# High-Current_Power_Supply.net
KiCad netlist of a schematic drawn in Altium Designer
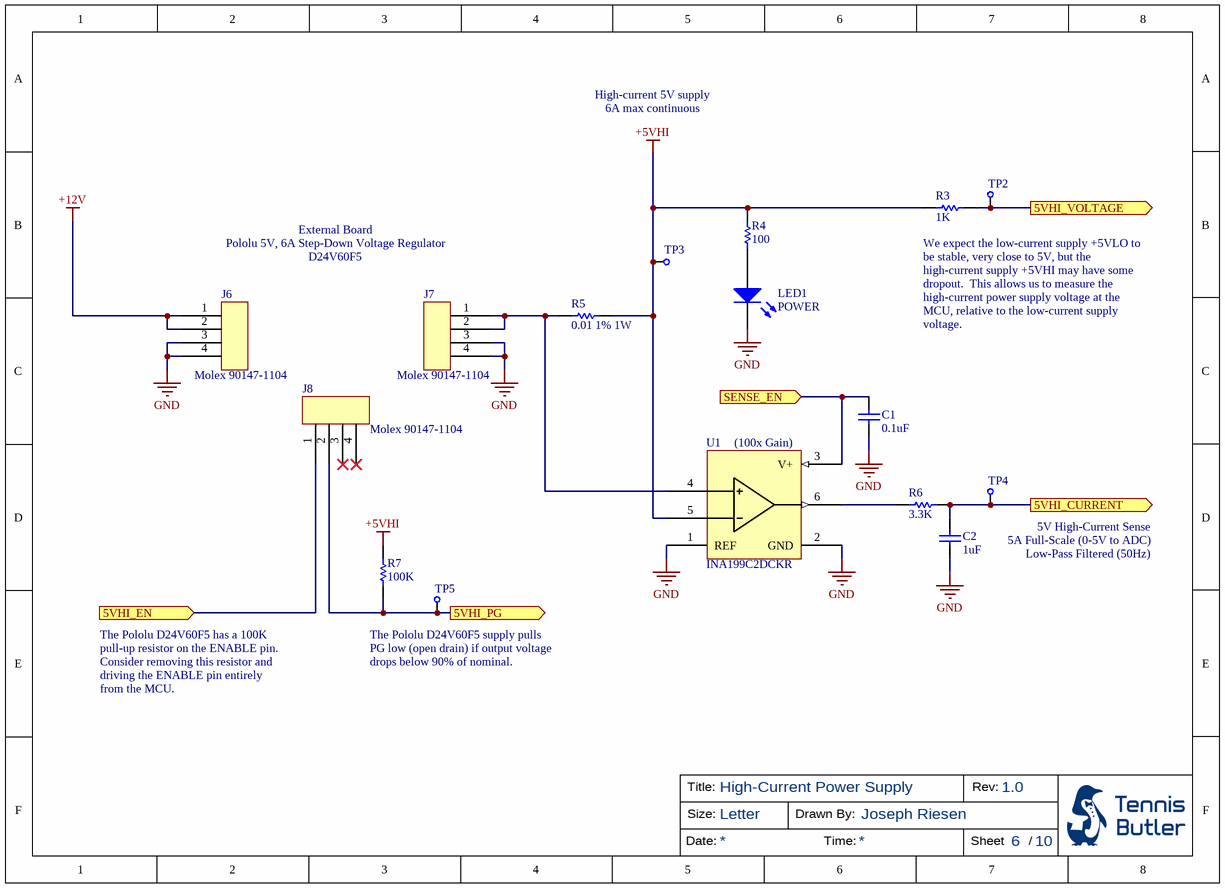
[diagram p0: High-Current Power Supply.SchDoc]

(export (version "E")
  (design (tool "Eeschema 10.0.6"))
  (components
    (comp (ref "C1")
      (value "0.1uF")
      (footprint "CAPC0805(2012)100_M")
      (description "CAP 100nF 6.3V ±10% 0805 (2012 Metric) Thickness 1mm SMD")
      (fields (field (name "TOLERANCE") "Â±10%"))
      (libsource (lib "Altium Content Vault") (part "CAP"))
    )
    (comp (ref "C2")
      (value "1uF")
      (footprint "CAPC2013X100X50ML20T25")
      (fields (field (name "MANUFACTURER") "Kemet") (field (name "PART NUMBER") "C0805C105K9RACTU"))
      (libsource (lib "Altium Content Vault") (part "CAP"))
    )
    (comp (ref "J6")
      (value "Molex 90147-1104")
      (footprint "Molex 90147-1104")
      (description "C-Grid® PC Board Connector, Single Row, Vertical, 4 Circuits, Tin (Sn) Plating")
      (fields (field (name "MANUFACTURER") "Molex") (field (name "MANUFACTURER PART NUMBER") "90147-1104"))
      (libsource (lib "") (part "Molex 90147-1104 C-Grid 4-Pin Header_1"))
    )
    (comp (ref "J7")
      (value "Molex 90147-1104")
      (footprint "Molex 90147-1104")
      (description "C-Grid® PC Board Connector, Single Row, Vertical, 4 Circuits, Tin (Sn) Plating")
      (fields (field (name "MANUFACTURER") "Molex") (field (name "MANUFACTURER PART NUMBER") "90147-1104"))
      (libsource (lib "TennisButler") (part "Molex 90147-1104 C-Grid 4-Pin Header"))
    )
    (comp (ref "J8")
      (value "Molex 90147-1104")
      (footprint "Molex 90147-1104")
      (description "C-Grid® PC Board Connector, Single Row, Vertical, 4 Circuits, Tin (Sn) Plating")
      (fields (field (name "MANUFACTURER") "Molex") (field (name "MANUFACTURER PART NUMBER") "90147-1104"))
      (libsource (lib "") (part "Molex 90147-1104 C-Grid 4-Pin Header_2"))
    )
    (comp (ref "LED1")
      (value "POWER")
      (footprint "0805_A")
      (description "SMD mono-color Chip LED, WL-SMCW, Blue")
      (fields (field (name "MANUFACTURER") "Wuerth Elektronik") (field (name "PARTNUMBER") "150080BS75000"))
      (libsource (lib "Altium Content Vault") (part "WE-LED_K1A2-2"))
    )
    (comp (ref "R3")
      (value "1K")
      (footprint "RESC2013X70X40ML20T20")
      (description "RES SMD 1K OHM 1% 1/8W 0805")
      (fields (field (name "PART NUMBER") "ERJ-6ENF1001V") (field (name "MANUFACTURER") "Panasonic"))
      (libsource (lib "Altium Content Vault") (part "RES"))
    )
    (comp (ref "R4")
      (value "100")
      (footprint "RESC2013X70X40ML20T20")
      (description "Chip Resistor, 100 Ohm, +/- 1%, 0.125 W, -55 to 155 degC, 0805 (2012 Metric), RoHS, Tape and Reel")
      (fields (field (name "MANUFACTURER") "Panasonic"))
      (libsource (lib "Altium Content Vault") (part "RES-2"))
    )
    (comp (ref "R5")
      (value "0.01 1% 1W")
      (footprint "RESC3216X70X50NL05T20")
      (fields (field (name "PART NUMBER") "ERJ8CWFR010V") (field (name "MANUFACTURER") "Panasonic"))
      (libsource (lib "Altium Content Vault") (part "RES"))
    )
    (comp (ref "R6")
      (value "3.3K")
      (footprint "RESC2013X70X40ML20T20")
      (description "RES SMD 3.3K OHM 1% 1/8W 0805")
      (fields (field (name "MANUFACTURER") "Panasonic") (field (name "PART NUMBER") "ERJ6ENF3301V"))
      (libsource (lib "Altium Content Vault") (part "RES"))
    )
    (comp (ref "R7")
      (value "100K")
      (footprint "RESC2013X70X40ML20T20")
      (description "RES SMD 100K OHM 1% 1/8W 0805")
      (fields (field (name "PART NUMBER") "ERJ-6ENF1003V") (field (name "MANUFACTURER") "Panasonic"))
      (libsource (lib "Altium Content Vault") (part "RES"))
    )
    (comp (ref "TP2")
      (value "5VHI VSENSE")
      (footprint "Test Point")
      (libsource (lib "Miscellaneous") (part "Test Point"))
    )
    (comp (ref "TP3")
      (value "+5VHI")
      (footprint "Test Point")
      (libsource (lib "Miscellaneous") (part "Test Point"))
    )
    (comp (ref "TP4")
      (value "5VHI CSENSE")
      (footprint "Test Point")
      (libsource (lib "Miscellaneous") (part "Test Point"))
    )
    (comp (ref "TP5")
      (value "5VHI PG")
      (footprint "Test Point")
      (libsource (lib "Miscellaneous") (part "Test Point"))
    )
    (comp (ref "U1")
      (value "INA199C2DCKR")
      (footprint "TSOP65P240X110-6M")
      (description "IC OP AMP CURR SENSE SC70-6")
      (fields (field (name "MANUFACTURER") "Texas Instruments"))
      (libsource (lib "INA199") (part "INA199C2DCKR"))
    )
  )
  (nets
    (net (code "1") (name "+5VHI") (class "Default")
      (node (ref "R3") (pin "1") (pinfunction "1_1") (pintype "passive"))
      (node (ref "R4") (pin "2") (pinfunction "2_2") (pintype "passive"))
      (node (ref "R5") (pin "2") (pinfunction "2_2") (pintype "passive"))
      (node (ref "R7") (pin "2") (pinfunction "2_2") (pintype "passive"))
      (node (ref "TP3") (pin "1") (pinfunction "1_1") (pintype "passive"))
      (node (ref "U1") (pin "5") (pinfunction "IN-_5") (pintype "passive"))
    )
    (net (code "2") (name "+12V") (class "Default")
      (node (ref "J6") (pin "1") (pintype "passive"))
      (node (ref "J6") (pin "2") (pintype "passive"))
    )
    (net (code "3") (name "/5VHI_CURRENT") (class "Default")
      (node (ref "C2") (pin "2") (pinfunction "2_2") (pintype "passive"))
      (node (ref "R6") (pin "2") (pinfunction "2_2") (pintype "passive"))
      (node (ref "TP4") (pin "1") (pinfunction "1_1") (pintype "passive"))
    )
    (net (code "4") (name "/5VHI_EN") (class "Default") (node (ref "J8") (pin "1") (pintype "passive")))
    (net (code "5") (name "/5VHI_PG") (class "Default")
      (node (ref "J8") (pin "2") (pintype "passive"))
      (node (ref "R7") (pin "1") (pinfunction "1_1") (pintype "passive"))
      (node (ref "TP5") (pin "1") (pinfunction "1_1") (pintype "passive"))
    )
    (net (code "6") (name "/5VHI_VOLTAGE") (class "Default")
      (node (ref "R3") (pin "2") (pinfunction "2_2") (pintype "passive"))
      (node (ref "TP2") (pin "1") (pinfunction "1_1") (pintype "passive"))
    )
    (net (code "7") (name "/SENSE_EN") (class "Default")
      (node (ref "C1") (pin "2") (pinfunction "2_2") (pintype "passive"))
      (node (ref "U1") (pin "3") (pinfunction "V+_3") (pintype "input"))
    )
    (net (code "8") (name "GND") (class "Default")
      (node (ref "C1") (pin "1") (pinfunction "1_1") (pintype "passive"))
      (node (ref "C2") (pin "1") (pinfunction "1_1") (pintype "passive"))
      (node (ref "J6") (pin "3") (pintype "passive"))
      (node (ref "J6") (pin "4") (pintype "passive"))
      (node (ref "J7") (pin "3") (pintype "passive"))
      (node (ref "J7") (pin "4") (pintype "passive"))
      (node (ref "LED1") (pin "1") (pinfunction "K_1") (pintype "passive"))
      (node (ref "U1") (pin "1") (pinfunction "REF_1") (pintype "passive"))
      (node (ref "U1") (pin "2") (pinfunction "GND_2") (pintype "power_in"))
    )
    (net (code "9") (name "Net-(LED1-A)") (class "Default")
      (node (ref "LED1") (pin "2") (pinfunction "A_2") (pintype "passive"))
      (node (ref "R4") (pin "1") (pinfunction "1_1") (pintype "passive"))
    )
    (net (code "10") (name "Net-(U1-IN+)") (class "Default")
      (node (ref "J7") (pin "1") (pintype "passive"))
      (node (ref "J7") (pin "2") (pintype "passive"))
      (node (ref "R5") (pin "1") (pinfunction "1_1") (pintype "passive"))
      (node (ref "U1") (pin "4") (pinfunction "IN+_4") (pintype "passive"))
    )
    (net (code "11") (name "Net-(U1-OUT)") (class "Default")
      (node (ref "R6") (pin "1") (pinfunction "1_1") (pintype "passive"))
      (node (ref "U1") (pin "6") (pinfunction "OUT_6") (pintype "output"))
    )
    (net (code "12") (name "unconnected-(J8-Pad3)") (class "Default")
      (node (ref "J8") (pin "3") (pintype "passive+no_connect"))
    )
    (net (code "13") (name "unconnected-(J8-Pad4)") (class "Default")
      (node (ref "J8") (pin "4") (pintype "passive+no_connect"))
    )
  )
)
